# TC264MCU.net
KiCad netlist of a schematic drawn in Altium Designer
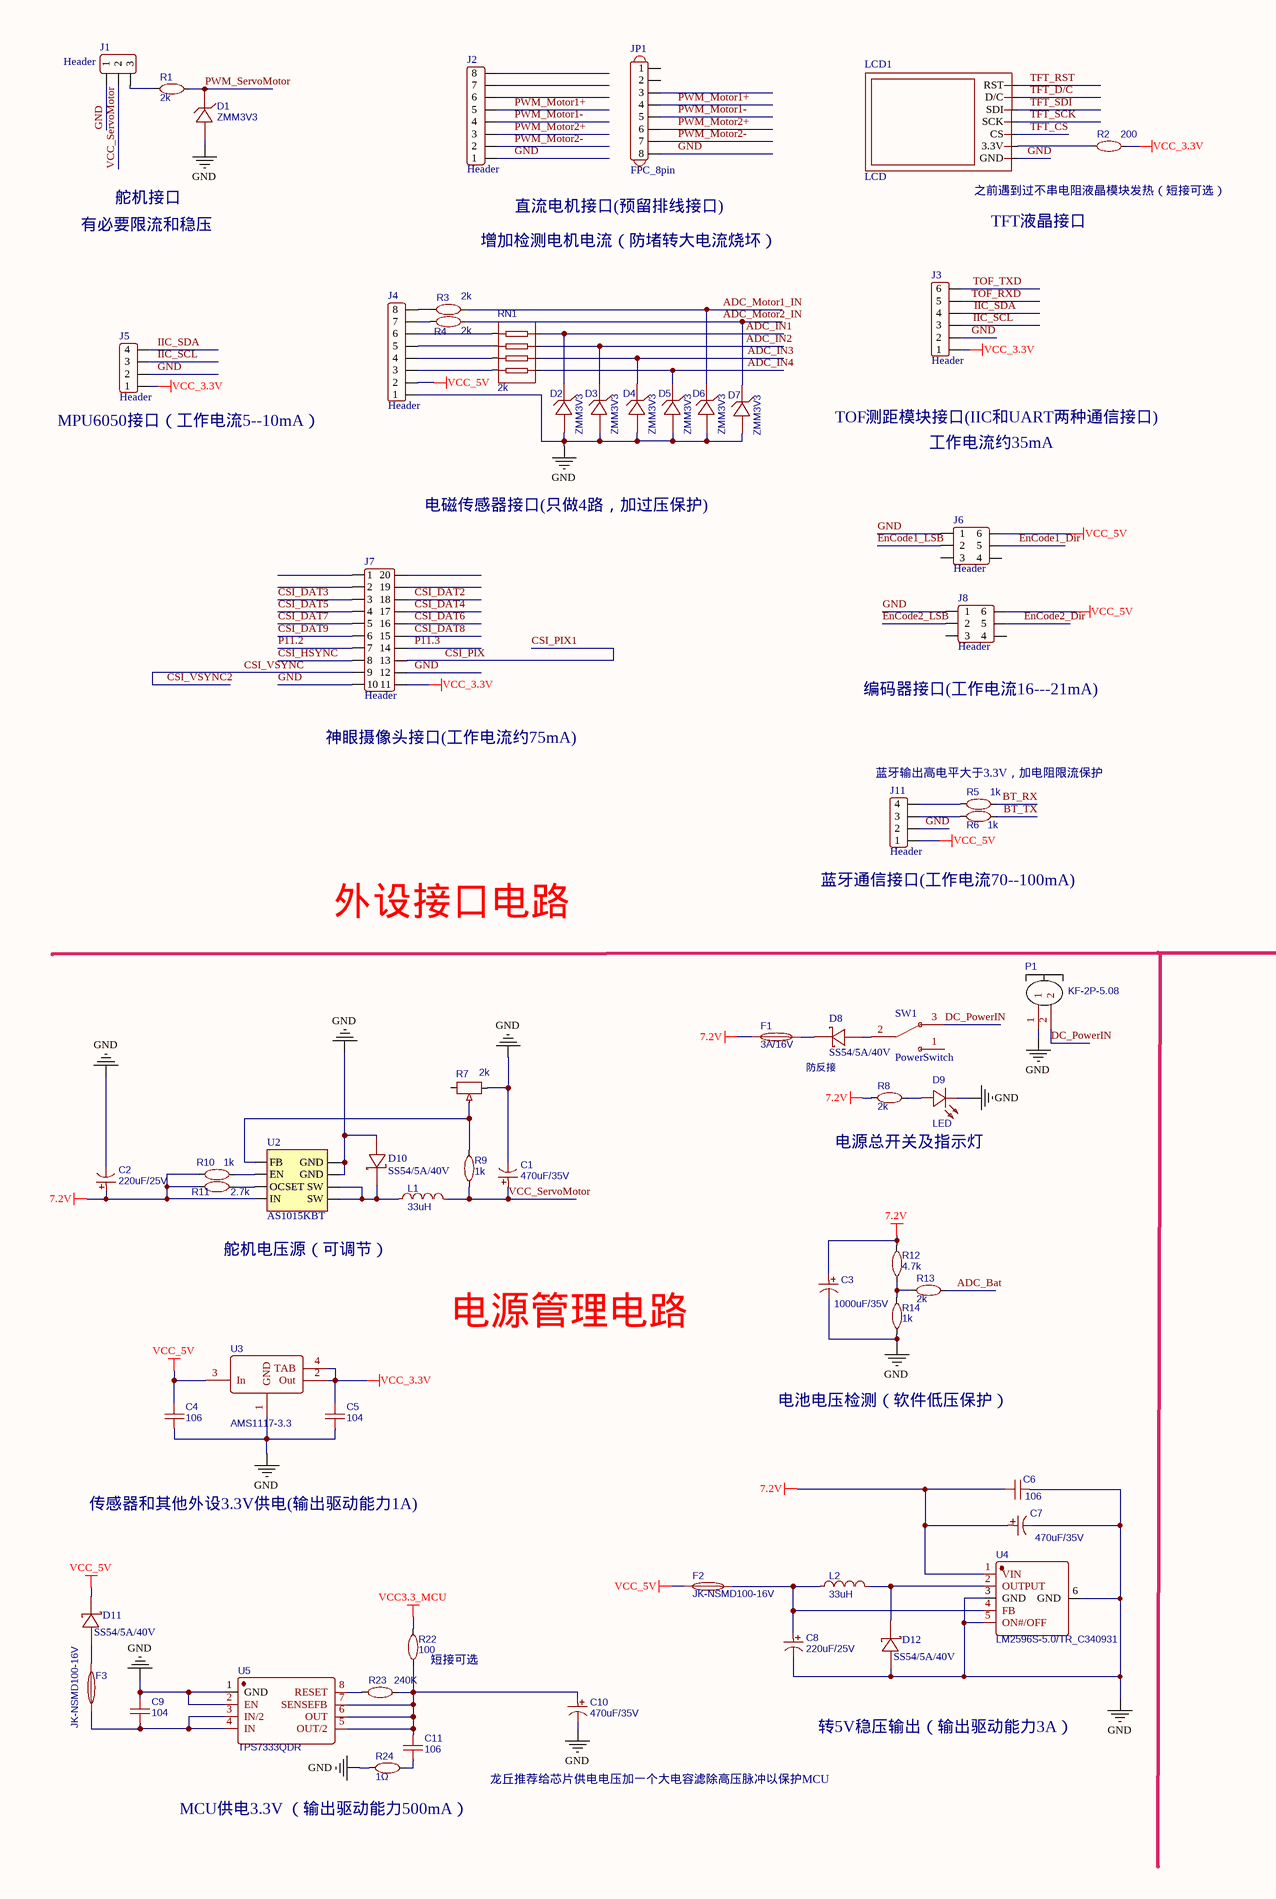
[diagram p0: TC264MCU.SchDoc, left]
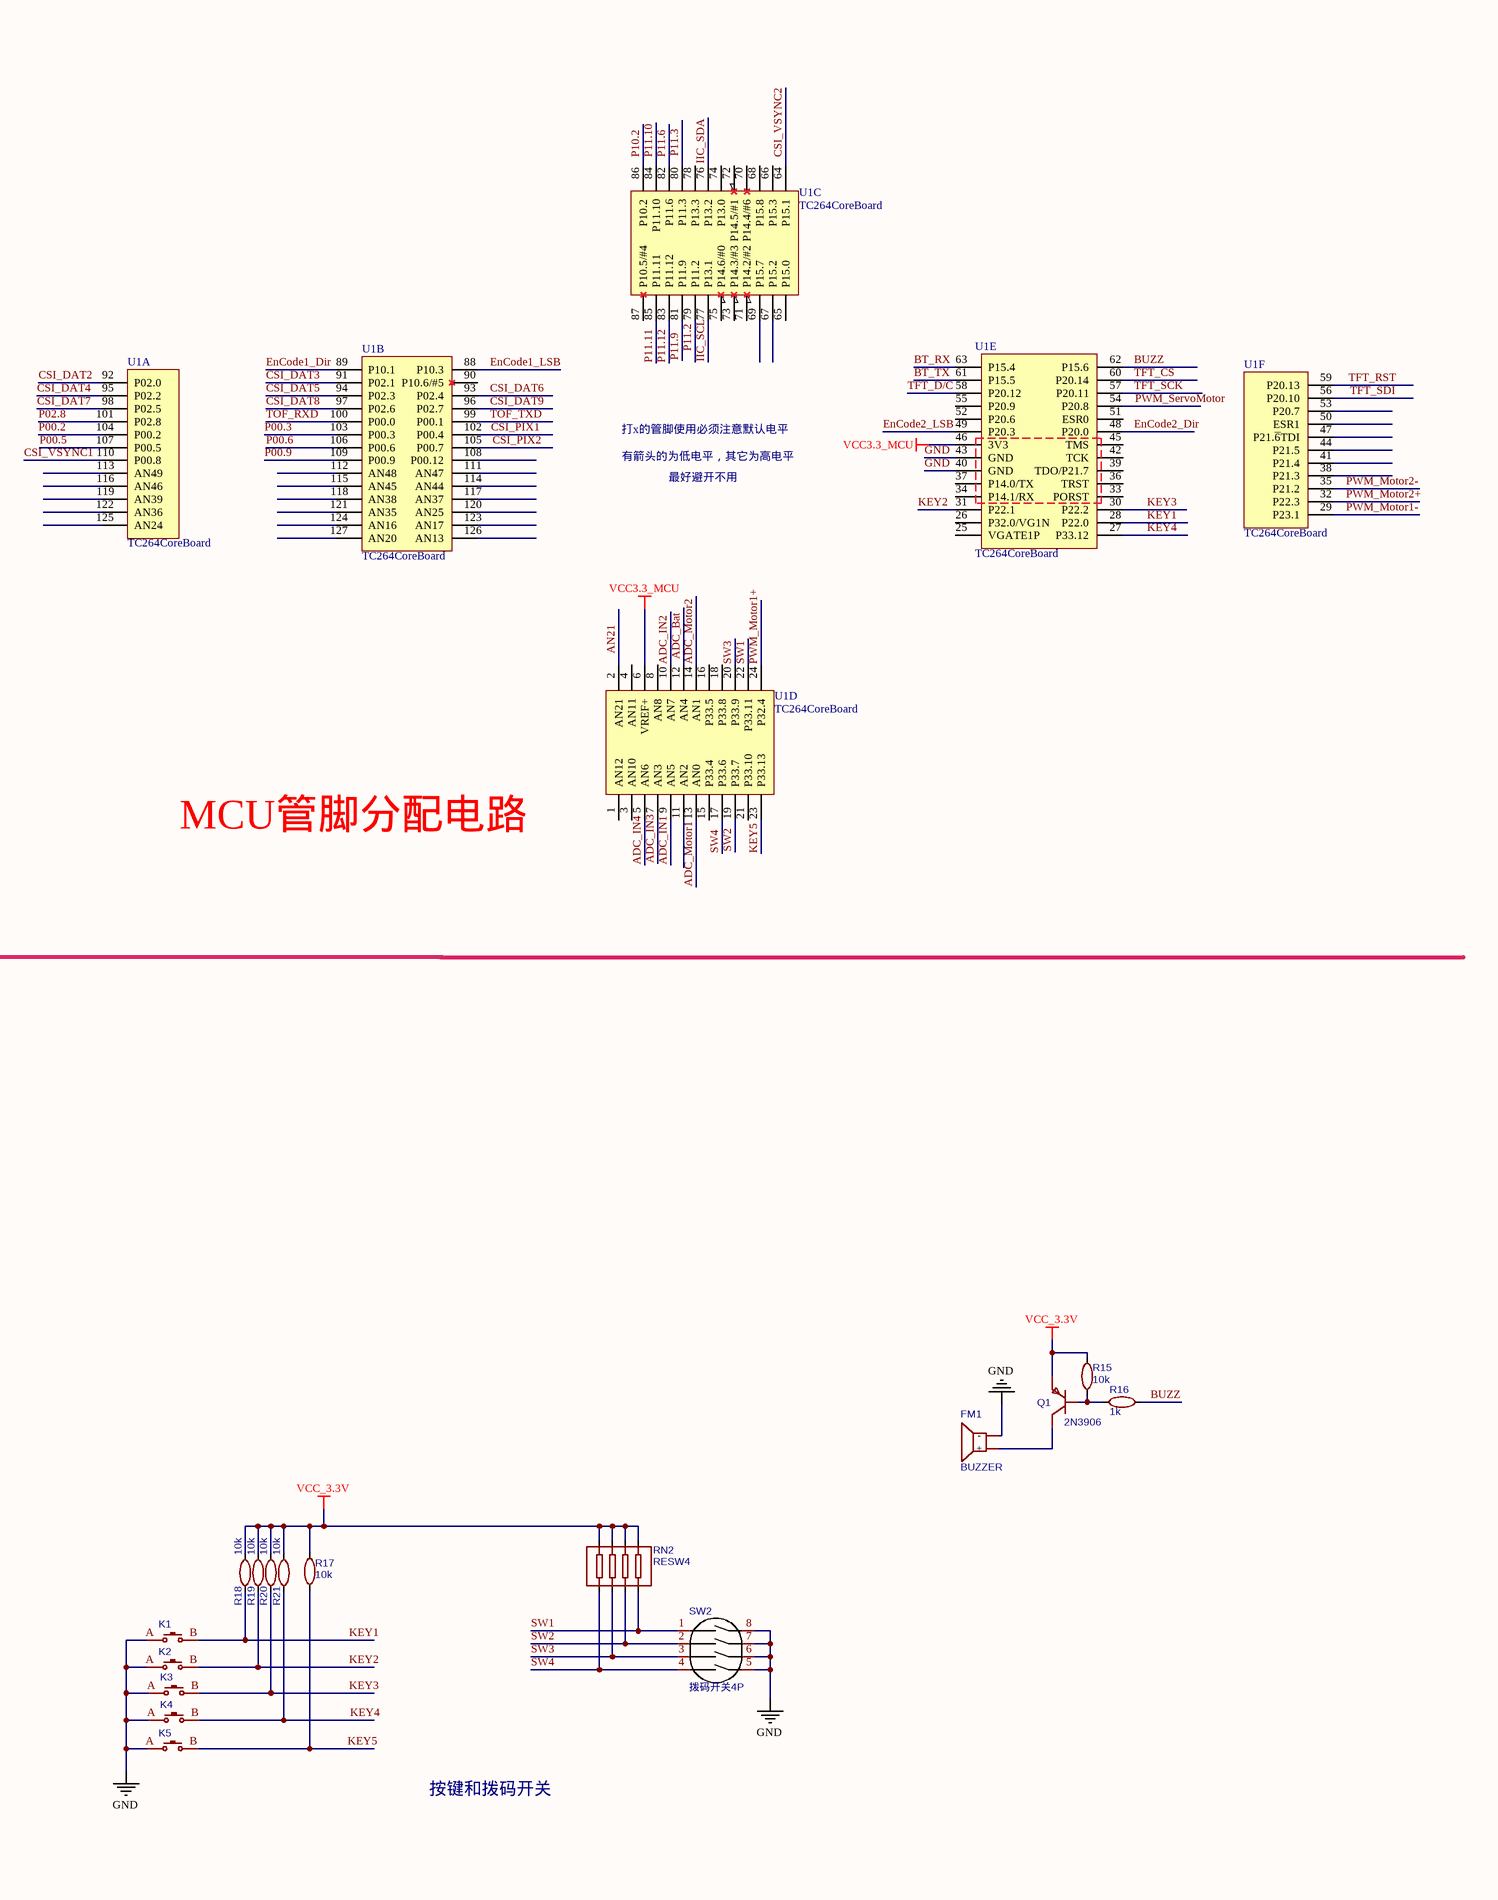
[diagram p1: TC264MCU.SchDoc, right]

(export (version "E")
  (design (tool "Eeschema 10.0.6"))
  (components
    (comp (ref "C1")
      (value "470uF/35V")
      (footprint "CAPE_SMD_G_10.6")
      (description "贴片电解电容")
      (fields
        (field (name "BOM_MANUFACTURER PART") "RVT1C221M0607")
        (field (name "BOM_SUPPLIER PART") "C72496")
      )
      (libsource (lib "") (part "CAP_E_SMD_1"))
    )
    (comp (ref "C2")
      (value "220uF/25V")
      (footprint "CAPE_SMD_F_8.4")
      (description "贴片电解电容")
      (fields
        (field (name "BOM_MANUFACTURER PART") "RVT1C221M0607")
        (field (name "BOM_SUPPLIER PART") "C72496")
      )
      (libsource (lib "") (part "CAP_E_SMD_1"))
    )
    (comp (ref "C3")
      (value "1000uF/35V")
      (footprint "CAPE_SMD_G_10.6")
      (description "贴片电解电容")
      (fields
        (field (name "BOM_MANUFACTURER PART") "RVT1C221M0607")
        (field (name "BOM_SUPPLIER PART") "C72496")
      )
      (libsource (lib "") (part "CAP_E_SMD_1"))
    )
    (comp (ref "C4")
      (value "106")
      (footprint "CAP_0603")
      (fields
        (field (name "BOM_SUPPLIER PART") "C307348")
        (field (name "BOM_MANUFACTURER PART") "CL10B104KB8WPNC")
        (field (name "CONTRIBUTOR") "LCSC")
      )
      (libsource (lib "LTC_Library1") (part "CAP_0603"))
    )
    (comp (ref "C5")
      (value "104")
      (footprint "CAP_0603")
      (fields
        (field (name "BOM_SUPPLIER PART") "C307348")
        (field (name "BOM_MANUFACTURER PART") "CL10B104KB8WPNC")
        (field (name "CONTRIBUTOR") "LCSC")
      )
      (libsource (lib "LTC_Library1") (part "CAP_0603"))
    )
    (comp (ref "C6")
      (value "106")
      (footprint "CAP_0603")
      (fields
        (field (name "BOM_SUPPLIER PART") "C307348")
        (field (name "BOM_MANUFACTURER PART") "CL10B104KB8WPNC")
        (field (name "CONTRIBUTOR") "LCSC")
      )
      (libsource (lib "LTC_Library1") (part "CAP_0603"))
    )
    (comp (ref "C7")
      (value "470uF/35V")
      (footprint "CAPE_SMD_G_10.6")
      (description "贴片电解电容")
      (fields
        (field (name "BOM_MANUFACTURER PART") "RVT1C221M0607")
        (field (name "BOM_SUPPLIER PART") "C72496")
      )
      (libsource (lib "LTC_Library1") (part "CAP_E_SMD"))
    )
    (comp (ref "C8")
      (value "220uF/25V")
      (footprint "CAPE_SMD_F_8.4")
      (description "贴片电解电容")
      (fields
        (field (name "BOM_MANUFACTURER PART") "RVT1C221M0607")
        (field (name "BOM_SUPPLIER PART") "C72496")
      )
      (libsource (lib "") (part "CAP_E_SMD_1"))
    )
    (comp (ref "C9")
      (value "104")
      (footprint "CAP_0603")
      (fields
        (field (name "BOM_SUPPLIER PART") "C307348")
        (field (name "BOM_MANUFACTURER PART") "CL10B104KB8WPNC")
        (field (name "CONTRIBUTOR") "LCSC")
      )
      (libsource (lib "LTC_Library1") (part "CAP_0603"))
    )
    (comp (ref "C10")
      (value "470uF/35V")
      (footprint "CAPE_SMD_G_10.6")
      (description "贴片电解电容")
      (fields
        (field (name "BOM_MANUFACTURER PART") "RVT1C221M0607")
        (field (name "BOM_SUPPLIER PART") "C72496")
      )
      (libsource (lib "") (part "CAP_E_SMD_1"))
    )
    (comp (ref "C11")
      (value "106")
      (footprint "CAP_0603")
      (fields
        (field (name "BOM_SUPPLIER PART") "C307348")
        (field (name "BOM_MANUFACTURER PART") "CL10B104KB8WPNC")
        (field (name "CONTRIBUTOR") "LCSC")
      )
      (libsource (lib "LTC_Library1") (part "CAP_0603"))
    )
    (comp (ref "D1")
      (value "ZMM3V3")
      (footprint "LL-34_L3.5-W1.5-RD")
      (fields (field (name "BOM_SUPPLIER PART") "C8056"))
      (libsource (lib "SmartCar_Library") (part "ZMM3V3"))
    )
    (comp (ref "D2")
      (value "ZMM3V3")
      (footprint "LL-34_L3.5-W1.5-RD")
      (fields (field (name "BOM_SUPPLIER PART") "C8056"))
      (libsource (lib "SmartCar_Library") (part "ZMM3V3"))
    )
    (comp (ref "D3")
      (value "ZMM3V3")
      (footprint "LL-34_L3.5-W1.5-RD")
      (fields (field (name "BOM_SUPPLIER PART") "C8056"))
      (libsource (lib "SmartCar_Library") (part "ZMM3V3"))
    )
    (comp (ref "D4")
      (value "ZMM3V3")
      (footprint "LL-34_L3.5-W1.5-RD")
      (fields (field (name "BOM_SUPPLIER PART") "C8056"))
      (libsource (lib "SmartCar_Library") (part "ZMM3V3"))
    )
    (comp (ref "D5")
      (value "ZMM3V3")
      (footprint "LL-34_L3.5-W1.5-RD")
      (fields (field (name "BOM_SUPPLIER PART") "C8056"))
      (libsource (lib "SmartCar_Library") (part "ZMM3V3"))
    )
    (comp (ref "D6")
      (value "ZMM3V3")
      (footprint "LL-34_L3.5-W1.5-RD")
      (fields (field (name "BOM_SUPPLIER PART") "C8056"))
      (libsource (lib "SmartCar_Library") (part "ZMM3V3"))
    )
    (comp (ref "D7")
      (value "ZMM3V3")
      (footprint "LL-34_L3.5-W1.5-RD")
      (fields (field (name "BOM_SUPPLIER PART") "C8056"))
      (libsource (lib "SmartCar_Library") (part "ZMM3V3"))
    )
    (comp (ref "D8")
      (value "SS54/5A/40V")
      (footprint "DO214_SMA")
      (libsource (lib "LTC_Library1") (part "SS54"))
    )
    (comp (ref "D9")
      (value "LED")
      (footprint "LED_0603_B")
      (description "发光LED")
      (fields
        (field (name "BOM_MANUFACTURER PART") "D-G080508G1")
        (field (name "BOM_SUPPLIER PART") "C107402")
        (field (name "CONTRIBUTOR") "LCSC")
      )
      (libsource (lib "LTC_Library1") (part "LED_0603"))
    )
    (comp (ref "D10")
      (value "SS54/5A/40V")
      (footprint "DO214_SMA")
      (libsource (lib "LTC_Library1") (part "SS54"))
    )
    (comp (ref "D11")
      (value "SS54/5A/40V")
      (footprint "DO214_SMA")
      (libsource (lib "LTC_Library1") (part "SS54"))
    )
    (comp (ref "D12")
      (value "SS54/5A/40V")
      (footprint "DO214_SMA")
      (libsource (lib "LTC_Library1") (part "SS54"))
    )
    (comp (ref "F1")
      (value "3A/16V")
      (footprint "F1206")
      (fields
        (field (name "BOM_SUPPLIER PART") "C369161")
        (field (name "BOM_MANUFACTURER PART") "JK-NSMD100-16V")
        (field (name "CONTRIBUTOR") "LCSC")
      )
      (libsource (lib "SmartCar_Library") (part "JK-NSMD100-16V"))
    )
    (comp (ref "F2")
      (value "JK-NSMD100-16V")
      (footprint "F1206")
      (fields (field (name "BOM_SUPPLIER PART") "C369161") (field (name "CONTRIBUTOR") "LCSC"))
      (libsource (lib "SmartCar_Library") (part "JK-NSMD100-16V"))
    )
    (comp (ref "F3")
      (value "JK-NSMD100-16V")
      (footprint "F1206")
      (fields (field (name "BOM_SUPPLIER PART") "C369161") (field (name "CONTRIBUTOR") "LCSC"))
      (libsource (lib "SmartCar_Library") (part "JK-NSMD100-16V"))
    )
    (comp (ref "FM1")
      (value "BUZZER")
      (footprint "BUZZ-12*7.5")
      (description "蜂鸣器")
      (fields (field (name "BOM_MANUFACTURER PART") "TMB12A12") (field (name "BOM_SUPPLIER PART") "C96079"))
      (libsource (lib "LTC_Library1") (part "BUZZER"))
    )
    (comp (ref "J1")
      (value "Header")
      (footprint "Header 2.54X3")
      (libsource (lib "LTC_Library1") (part "Header 2.54_3"))
    )
    (comp (ref "J2")
      (value "Header")
      (footprint "Header 2.54X8")
      (libsource (lib "LTC_Library1") (part "Header 2.54_8"))
    )
    (comp (ref "J3")
      (value "Header")
      (footprint "Header 2.54X6")
      (libsource (lib "LTC_Library1") (part "Header 2.54_6"))
    )
    (comp (ref "J4")
      (value "Header")
      (footprint "Header 2.54X8")
      (libsource (lib "LTC_Library1") (part "Header 2.54_8"))
    )
    (comp (ref "J5")
      (value "Header")
      (footprint "Header 2.54X4")
      (libsource (lib "LTC_Library1") (part "Header 2.54_4"))
    )
    (comp (ref "J6")
      (value "Header")
      (footprint "Header 2.54_2X3")
      (libsource (lib "LTC_Library1") (part "Header 2.54_2X3"))
    )
    (comp (ref "J7")
      (value "Header")
      (footprint "Header F 2.54_2x10")
      (libsource (lib "LTC_Library1") (part "Header 2.54_2X10"))
    )
    (comp (ref "J8")
      (value "Header")
      (footprint "Header 2.54_2X3")
      (libsource (lib "LTC_Library1") (part "Header 2.54_2X3"))
    )
    (comp (ref "J11")
      (value "Header")
      (footprint "Header F 2.54X4")
      (libsource (lib "LTC_Library1") (part "Header 2.54_4"))
    )
    (comp (ref "JP1")
      (value "FPC_8pin")
      (footprint "FPC_1.0_8P")
      (libsource (lib "LTC_Library1") (part "FPC_8pin"))
    )
    (comp (ref "K1")
      (value "TS-Button_2P")
      (footprint "SW_SMD_6.1*3.7")
      (description "贴片按键 3*6*2.5")
      (fields
        (field (name "BOM_SUPPLIER PART") "C455236")
        (field (name "BOM_MANUFACTURER PART") "TS-1007S-26")
        (field (name "CONTRIBUTOR") "LCSC")
      )
      (libsource (lib "LTC_Library1") (part "TS-Button_2P"))
    )
    (comp (ref "K2")
      (value "TS-Button_2P")
      (footprint "SW_SMD_6.1*3.7")
      (description "贴片按键 3*6*2.5")
      (fields
        (field (name "BOM_SUPPLIER PART") "C455236")
        (field (name "BOM_MANUFACTURER PART") "TS-1007S-26")
        (field (name "CONTRIBUTOR") "LCSC")
      )
      (libsource (lib "LTC_Library1") (part "TS-Button_2P"))
    )
    (comp (ref "K3")
      (value "TS-Button_2P")
      (footprint "SW_SMD_6.1*3.7")
      (description "贴片按键 3*6*2.5")
      (fields
        (field (name "BOM_SUPPLIER PART") "C455236")
        (field (name "BOM_MANUFACTURER PART") "TS-1007S-26")
        (field (name "CONTRIBUTOR") "LCSC")
      )
      (libsource (lib "LTC_Library1") (part "TS-Button_2P"))
    )
    (comp (ref "K4")
      (value "TS-Button_2P")
      (footprint "SW_SMD_6.1*3.7")
      (description "贴片按键 3*6*2.5")
      (fields
        (field (name "BOM_SUPPLIER PART") "C455236")
        (field (name "BOM_MANUFACTURER PART") "TS-1007S-26")
        (field (name "CONTRIBUTOR") "LCSC")
      )
      (libsource (lib "LTC_Library1") (part "TS-Button_2P"))
    )
    (comp (ref "K5")
      (value "TS-Button_2P")
      (footprint "SW_SMD_6.1*3.7")
      (description "贴片按键 3*6*2.5")
      (fields
        (field (name "BOM_SUPPLIER PART") "C455236")
        (field (name "BOM_MANUFACTURER PART") "TS-1007S-26")
        (field (name "CONTRIBUTOR") "LCSC")
      )
      (libsource (lib "LTC_Library1") (part "TS-Button_2P"))
    )
    (comp (ref "L1")
      (value "33uH")
      (footprint "IND-SMD_L8.0-W8.0")
      (fields
        (field (name "BOM_SUPPLIER PART") "C295130")
        (field (name "BOM_MANUFACTURER PART") "NLV25T-330J-EF")
        (field (name "CONTRIBUTOR") "LCSC")
      )
      (libsource (lib "SmartCar_Library") (part "Inductor"))
    )
    (comp (ref "L2")
      (value "33uH")
      (footprint "IND-SMD_L8.0-W8.0")
      (fields
        (field (name "BOM_SUPPLIER PART") "C295130")
        (field (name "BOM_MANUFACTURER PART") "NLV25T-330J-EF")
        (field (name "CONTRIBUTOR") "LCSC")
      )
      (libsource (lib "SmartCar_Library") (part "Inductor"))
    )
    (comp (ref "LCD1")
      (value "LCD")
      (footprint "TFT_LCD")
      (libsource (lib "SmartCar_Library") (part "TFT-LCD"))
    )
    (comp (ref "P1")
      (value "KF-2P-5.08")
      (footprint "KF_2P-5.08")
      (description "端子2P")
      (fields
        (field (name "BOM_MANUFACTURER PART") "WJ500H-5.08-2P")
        (field (name "BOM_SUPPLIER PART") "C8478")
      )
      (libsource (lib "LTC_Library1") (part "KF-2P-5.08"))
    )
    (comp (ref "Q1")
      (value "2N3906")
      (footprint "TO_92A")
      (description "三极管PNP")
      (fields (field (name "BOM_SUPPLIER PART") "C305396") (field (name "CONTRIBUTOR") "LCSC"))
      (libsource (lib "LTC_Library1") (part "2N3906"))
    )
    (comp (ref "R1")
      (value "2k")
      (footprint "RES_0603")
      (fields
        (field (name "BOM_MANUFACTURER PART") "RC0402JR-07100KL")
        (field (name "BOM_SUPPLIER PART") "C106234")
      )
      (libsource (lib "LTC_Library1") (part "RES_0603"))
    )
    (comp (ref "R2")
      (value "200")
      (footprint "RES_0603")
      (fields
        (field (name "BOM_MANUFACTURER PART") "RC0402JR-07100KL")
        (field (name "BOM_SUPPLIER PART") "C106234")
      )
      (libsource (lib "LTC_Library1") (part "RES_0603"))
    )
    (comp (ref "R3")
      (value "2k")
      (footprint "RES_0603")
      (fields
        (field (name "BOM_MANUFACTURER PART") "RC0402JR-07100KL")
        (field (name "BOM_SUPPLIER PART") "C106234")
      )
      (libsource (lib "LTC_Library1") (part "RES_0603"))
    )
    (comp (ref "R4")
      (value "2k")
      (footprint "RES_0603")
      (fields
        (field (name "BOM_MANUFACTURER PART") "RC0402JR-07100KL")
        (field (name "BOM_SUPPLIER PART") "C106234")
      )
      (libsource (lib "LTC_Library1") (part "RES_0603"))
    )
    (comp (ref "R5")
      (value "1k")
      (footprint "RES_0603")
      (fields
        (field (name "BOM_MANUFACTURER PART") "RC0402JR-07100KL")
        (field (name "BOM_SUPPLIER PART") "C106234")
      )
      (libsource (lib "LTC_Library1") (part "RES_0603"))
    )
    (comp (ref "R6")
      (value "1k")
      (footprint "RES_0603")
      (fields
        (field (name "BOM_MANUFACTURER PART") "RC0402JR-07100KL")
        (field (name "BOM_SUPPLIER PART") "C106234")
      )
      (libsource (lib "LTC_Library1") (part "RES_0603"))
    )
    (comp (ref "R7")
      (value "2k")
      (footprint "RES_POT-3296W")
      (description "可调电阻3296W")
      (fields
        (field (name "BOM_SUPPLIER PART") "C118963")
        (field (name "BOM_MANUFACTURER PART") "3296W-1-104")
        (field (name "CONTRIBUTOR") "LCSC")
      )
      (libsource (lib "LTC_Library1") (part "RES_POT-3296W"))
    )
    (comp (ref "R8")
      (value "2k")
      (footprint "RES_0603")
      (fields
        (field (name "BOM_MANUFACTURER PART") "RC0402JR-07100KL")
        (field (name "BOM_SUPPLIER PART") "C106234")
      )
      (libsource (lib "LTC_Library1") (part "RES_0603"))
    )
    (comp (ref "R9")
      (value "1k")
      (footprint "RES_0603")
      (fields
        (field (name "BOM_MANUFACTURER PART") "RC0402JR-07100KL")
        (field (name "BOM_SUPPLIER PART") "C106234")
      )
      (libsource (lib "LTC_Library1") (part "RES_0603"))
    )
    (comp (ref "R10")
      (value "1k")
      (footprint "RES_0603")
      (fields
        (field (name "BOM_MANUFACTURER PART") "RC0402JR-07100KL")
        (field (name "BOM_SUPPLIER PART") "C106234")
      )
      (libsource (lib "LTC_Library1") (part "RES_0603"))
    )
    (comp (ref "R11")
      (value "2.7k")
      (footprint "RES_0603")
      (fields
        (field (name "BOM_MANUFACTURER PART") "RC0402JR-07100KL")
        (field (name "BOM_SUPPLIER PART") "C106234")
      )
      (libsource (lib "LTC_Library1") (part "RES_0603"))
    )
    (comp (ref "R12")
      (value "4.7k")
      (footprint "RES_0603")
      (fields
        (field (name "BOM_MANUFACTURER PART") "RC0402JR-07100KL")
        (field (name "BOM_SUPPLIER PART") "C106234")
      )
      (libsource (lib "LTC_Library1") (part "RES_0603"))
    )
    (comp (ref "R13")
      (value "2k")
      (footprint "RES_0603")
      (fields
        (field (name "BOM_MANUFACTURER PART") "RC0402JR-07100KL")
        (field (name "BOM_SUPPLIER PART") "C106234")
      )
      (libsource (lib "LTC_Library1") (part "RES_0603"))
    )
    (comp (ref "R14")
      (value "1k")
      (footprint "RES_0603")
      (fields
        (field (name "BOM_MANUFACTURER PART") "RC0402JR-07100KL")
        (field (name "BOM_SUPPLIER PART") "C106234")
      )
      (libsource (lib "LTC_Library1") (part "RES_0603"))
    )
    (comp (ref "R15")
      (value "10k")
      (footprint "RES_0603")
      (fields
        (field (name "BOM_MANUFACTURER PART") "RC0402JR-07100KL")
        (field (name "BOM_SUPPLIER PART") "C106234")
      )
      (libsource (lib "LTC_Library1") (part "RES_0603"))
    )
    (comp (ref "R16")
      (value "1k")
      (footprint "RES_0603")
      (fields
        (field (name "BOM_MANUFACTURER PART") "RC0402JR-07100KL")
        (field (name "BOM_SUPPLIER PART") "C106234")
      )
      (libsource (lib "LTC_Library1") (part "RES_0603"))
    )
    (comp (ref "R17")
      (value "10k")
      (footprint "RES_0603")
      (fields
        (field (name "BOM_MANUFACTURER PART") "RC0402JR-07100KL")
        (field (name "BOM_SUPPLIER PART") "C106234")
      )
      (libsource (lib "LTC_Library1") (part "RES_0603"))
    )
    (comp (ref "R18")
      (value "10k")
      (footprint "RES_0603")
      (fields
        (field (name "BOM_MANUFACTURER PART") "RC0402JR-07100KL")
        (field (name "BOM_SUPPLIER PART") "C106234")
      )
      (libsource (lib "LTC_Library1") (part "RES_0603"))
    )
    (comp (ref "R19")
      (value "10k")
      (footprint "RES_0603")
      (fields
        (field (name "BOM_MANUFACTURER PART") "RC0402JR-07100KL")
        (field (name "BOM_SUPPLIER PART") "C106234")
      )
      (libsource (lib "LTC_Library1") (part "RES_0603"))
    )
    (comp (ref "R20")
      (value "10k")
      (footprint "RES_0603")
      (fields
        (field (name "BOM_MANUFACTURER PART") "RC0402JR-07100KL")
        (field (name "BOM_SUPPLIER PART") "C106234")
      )
      (libsource (lib "LTC_Library1") (part "RES_0603"))
    )
    (comp (ref "R21")
      (value "10k")
      (footprint "RES_0603")
      (fields
        (field (name "BOM_MANUFACTURER PART") "RC0402JR-07100KL")
        (field (name "BOM_SUPPLIER PART") "C106234")
      )
      (libsource (lib "LTC_Library1") (part "RES_0603"))
    )
    (comp (ref "R22")
      (value "100")
      (footprint "RES_0603")
      (fields
        (field (name "BOM_MANUFACTURER PART") "RC0402JR-07100KL")
        (field (name "BOM_SUPPLIER PART") "C106234")
      )
      (libsource (lib "LTC_Library1") (part "RES_0603"))
    )
    (comp (ref "R23")
      (value "240K")
      (footprint "RES_0603")
      (fields
        (field (name "BOM_MANUFACTURER PART") "RC0402JR-07100KL")
        (field (name "BOM_SUPPLIER PART") "C106234")
      )
      (libsource (lib "LTC_Library1") (part "RES_0603"))
    )
    (comp (ref "R24")
      (value "1Ω")
      (footprint "RES_0603")
      (fields
        (field (name "BOM_MANUFACTURER PART") "RC0402JR-07100KL")
        (field (name "BOM_SUPPLIER PART") "C106234")
      )
      (libsource (lib "LTC_Library1") (part "RES_0603"))
    )
    (comp (ref "RN1")
      (value "2k")
      (footprint "RES-ARRAY-SMD_0603-8P-L3.2-W1.6-BL")
      (fields
        (field (name "BOM_MANUFACTURER PART") "YC164-JR-0710KL")
        (field (name "BOM_SUPPLIER PART") "C107374")
      )
      (libsource (lib "SmartCar_Library") (part "RESW4"))
    )
    (comp (ref "RN2")
      (value "RESW4")
      (footprint "RES-ARRAY-SMD_0603-8P-L3.2-W1.6-BL")
      (fields
        (field (name "BOM_MANUFACTURER PART") "YC164-JR-0710KL")
        (field (name "BOM_SUPPLIER PART") "C107374")
      )
      (libsource (lib "SmartCar_Library") (part "RESW4"))
    )
    (comp (ref "SW1")
      (value "PowerSwitch")
      (footprint "SW-TH_K3-1260D-K1")
      (libsource (lib "SmartCar_Library") (part "PowerSwitch"))
    )
    (comp (ref "SW2")
      (value "拨码开关4P")
      (footprint "MCEMR-04-T")
      (description "DIP_4PX2*2.54")
      (fields
        (field (name "BOM_MANUFACTURER PART") "VDG/S-04HG-R")
        (field (name "BOM_SUPPLIER PART") "C15781")
      )
      (libsource (lib "LTC_Library1") (part "拨码开关4P"))
    )
    (comp (ref "U1")
      (value "TC264CoreBoard")
      (footprint "LQ-TC264-SYSVC-S")
      (libsource (lib "SmartCar_Library") (part "TC264CoreBoard"))
    )
    (comp (ref "U2")
      (value "AS1015KBT")
      (footprint "SOIC-8_150MIL")
      (libsource (lib "SmartCar_Library") (part "AS1015KBT"))
    )
    (comp (ref "U3")
      (value "AMS1117-3.3")
      (footprint "SOT-223_3")
      (fields (field (name "BOM_SUPPLIER PART") "C165482") (field (name "CONTRIBUTOR") "LCSC"))
      (libsource (lib "LTC_Library1") (part "AMS1117-3.3"))
    )
    (comp (ref "U4")
      (value "LM2596S-5.0/TR_C340931")
      (footprint "TO-263_5")
      (fields
        (field (name "BOM_SUPPLIER PART") "C340931")
        (field (name "BOM_MANUFACTURER PART") "LM2596S-5.0/TR")
        (field (name "CONTRIBUTOR") "LCSC")
      )
      (libsource (lib "LTC_Library1") (part "LM2596S-5.0/TR_C340931"))
    )
    (comp (ref "U5")
      (value "TPS7333QDR")
      (footprint "SOIC-8_150MIL")
      (fields (field (name "BOM_SUPPLIER PART") "C23791"))
      (libsource (lib "LTC_Library1") (part "TPS7333QDR"))
    )
  )
  (nets
    (net (code "1") (name "/ADC_Bat") (class "Default")
      (node (ref "R13") (pin "2") (pinfunction "2_2") (pintype "passive"))
      (node (ref "U1") (pin "12") (pinfunction "AN4_12") (pintype "passive"))
    )
    (net (code "2") (name "/ADC_IN1") (class "Default")
      (node (ref "D2") (pin "1") (pinfunction "C_1") (pintype "passive"))
      (node (ref "RN1") (pin "8") (pinfunction "8_8") (pintype "passive"))
      (node (ref "U1") (pin "9") (pinfunction "AN5_9") (pintype "passive"))
    )
    (net (code "3") (name "/ADC_IN2") (class "Default")
      (node (ref "D3") (pin "1") (pinfunction "C_1") (pintype "passive"))
      (node (ref "RN1") (pin "7") (pinfunction "7_7") (pintype "passive"))
      (node (ref "U1") (pin "10") (pinfunction "AN7_10") (pintype "passive"))
    )
    (net (code "4") (name "/ADC_IN3") (class "Default")
      (node (ref "D4") (pin "1") (pinfunction "C_1") (pintype "passive"))
      (node (ref "RN1") (pin "6") (pinfunction "6_6") (pintype "passive"))
      (node (ref "U1") (pin "7") (pinfunction "AN3_7") (pintype "passive"))
    )
    (net (code "5") (name "/ADC_IN4") (class "Default")
      (node (ref "D5") (pin "1") (pinfunction "C_1") (pintype "passive"))
      (node (ref "RN1") (pin "5") (pinfunction "5_5") (pintype "passive"))
      (node (ref "U1") (pin "5") (pinfunction "AN6_5") (pintype "passive"))
    )
    (net (code "6") (name "/ADC_Motor1") (class "Default")
      (node (ref "U1") (pin "13") (pinfunction "AN0_13") (pintype "passive"))
    )
    (net (code "7") (name "/ADC_Motor1_IN") (class "Default")
      (node (ref "D6") (pin "1") (pinfunction "C_1") (pintype "passive"))
      (node (ref "R3") (pin "1") (pinfunction "1_1") (pintype "passive"))
    )
    (net (code "8") (name "/ADC_Motor2") (class "Default")
      (node (ref "U1") (pin "14") (pinfunction "AN1_14") (pintype "passive"))
    )
    (net (code "9") (name "/ADC_Motor2_IN") (class "Default")
      (node (ref "D7") (pin "1") (pinfunction "C_1") (pintype "passive"))
      (node (ref "R4") (pin "1") (pinfunction "1_1") (pintype "passive"))
    )
    (net (code "10") (name "/AN21") (class "Default")
      (node (ref "U1") (pin "2") (pinfunction "AN21_2") (pintype "passive"))
    )
    (net (code "11") (name "/BT_RX") (class "Default")
      (node (ref "R5") (pin "1") (pinfunction "1_1") (pintype "passive"))
      (node (ref "U1") (pin "63") (pinfunction "P15.4_63") (pintype "passive"))
    )
    (net (code "12") (name "/BT_TX") (class "Default")
      (node (ref "R6") (pin "1") (pinfunction "1_1") (pintype "passive"))
      (node (ref "U1") (pin "61") (pinfunction "P15.5_61") (pintype "passive"))
    )
    (net (code "13") (name "/BUZZ") (class "Default")
      (node (ref "R16") (pin "1") (pinfunction "1_1") (pintype "passive"))
      (node (ref "U1") (pin "62") (pinfunction "P15.6_62") (pintype "passive"))
    )
    (net (code "14") (name "/CSI_DAT2") (class "Default")
      (node (ref "J7") (pin "18") (pinfunction "18_18") (pintype "passive"))
      (node (ref "U1") (pin "92") (pinfunction "P02.0_92") (pintype "passive"))
    )
    (net (code "15") (name "/CSI_DAT3") (class "Default")
      (node (ref "J7") (pin "3") (pinfunction "3_3") (pintype "passive"))
      (node (ref "U1") (pin "91") (pinfunction "P02.1_91") (pintype "passive"))
    )
    (net (code "16") (name "/CSI_DAT4") (class "Default")
      (node (ref "J7") (pin "17") (pinfunction "17_17") (pintype "passive"))
      (node (ref "U1") (pin "95") (pinfunction "P02.2_95") (pintype "passive"))
    )
    (net (code "17") (name "/CSI_DAT5") (class "Default")
      (node (ref "J7") (pin "4") (pinfunction "4_4") (pintype "passive"))
      (node (ref "U1") (pin "94") (pinfunction "P02.3_94") (pintype "passive"))
    )
    (net (code "18") (name "/CSI_DAT6") (class "Default")
      (node (ref "J7") (pin "16") (pinfunction "16_16") (pintype "passive"))
      (node (ref "U1") (pin "93") (pinfunction "P02.4_93") (pintype "passive"))
    )
    (net (code "19") (name "/CSI_DAT7") (class "Default")
      (node (ref "J7") (pin "5") (pinfunction "5_5") (pintype "passive"))
      (node (ref "U1") (pin "98") (pinfunction "P02.5_98") (pintype "passive"))
    )
    (net (code "20") (name "/CSI_DAT8") (class "Default")
      (node (ref "J7") (pin "15") (pinfunction "15_15") (pintype "passive"))
      (node (ref "U1") (pin "97") (pinfunction "P02.6_97") (pintype "passive"))
    )
    (net (code "21") (name "/CSI_DAT9") (class "Default")
      (node (ref "J7") (pin "6") (pinfunction "6_6") (pintype "passive"))
      (node (ref "U1") (pin "96") (pinfunction "P02.7_96") (pintype "passive"))
    )
    (net (code "22") (name "/CSI_HSYNC") (class "Default")
      (node (ref "J7") (pin "8") (pinfunction "8_8") (pintype "passive"))
    )
    (net (code "23") (name "/CSI_PIX") (class "Default")
      (node (ref "J7") (pin "13") (pinfunction "13_13") (pintype "passive"))
      (node (ref "U1") (pin "102") (pinfunction "P00.4_102") (pintype "passive"))
    )
    (net (code "24") (name "/CSI_PIX2") (class "Default")
      (node (ref "U1") (pin "105") (pinfunction "P00.7_105") (pintype "passive"))
    )
    (net (code "25") (name "/CSI_VSYNC") (class "Default")
      (node (ref "J7") (pin "9") (pinfunction "9_9") (pintype "passive"))
      (node (ref "U1") (pin "64") (pinfunction "P15.1_64") (pintype "passive"))
    )
    (net (code "26") (name "/CSI_VSYNC1") (class "Default")
      (node (ref "U1") (pin "110") (pinfunction "P00.8_110") (pintype "passive"))
    )
    (net (code "27") (name "/DC_PowerIN") (class "Default")
      (node (ref "P1") (pin "2") (pinfunction "2_2") (pintype "passive"))
      (node (ref "SW1") (pin "3") (pinfunction "NC_3") (pintype "passive"))
    )
    (net (code "28") (name "/EnCode1_Dir") (class "Default")
      (node (ref "J6") (pin "5") (pinfunction "5_5") (pintype "passive"))
      (node (ref "U1") (pin "89") (pinfunction "P10.1_89") (pintype "passive"))
    )
    (net (code "29") (name "/EnCode1_LSB") (class "Default")
      (node (ref "J6") (pin "2") (pinfunction "2_2") (pintype "passive"))
      (node (ref "U1") (pin "88") (pinfunction "P10.3_88") (pintype "passive"))
    )
    (net (code "30") (name "/EnCode2_Dir") (class "Default")
      (node (ref "J8") (pin "5") (pinfunction "5_5") (pintype "passive"))
      (node (ref "U1") (pin "48") (pinfunction "P20.0_48") (pintype "passive"))
    )
    (net (code "31") (name "/EnCode2_LSB") (class "Default")
      (node (ref "J8") (pin "2") (pinfunction "2_2") (pintype "passive"))
      (node (ref "U1") (pin "49") (pinfunction "P20.3_49") (pintype "passive"))
    )
    (net (code "32") (name "/IIC_SCL") (class "Default")
      (node (ref "J3") (pin "3") (pinfunction "3_3") (pintype "passive"))
      (node (ref "J5") (pin "3") (pinfunction "3_3") (pintype "passive"))
      (node (ref "U1") (pin "77") (pinfunction "P13.1_77") (pintype "passive"))
    )
    (net (code "33") (name "/IIC_SDA") (class "Default")
      (node (ref "J3") (pin "4") (pinfunction "4_4") (pintype "passive"))
      (node (ref "J5") (pin "4") (pinfunction "4_4") (pintype "passive"))
      (node (ref "U1") (pin "76") (pinfunction "P13.2_76") (pintype "passive"))
    )
    (net (code "34") (name "/KEY1") (class "Default")
      (node (ref "K1") (pin "B") (pinfunction "B_B") (pintype "passive"))
      (node (ref "R18") (pin "1") (pinfunction "1_1") (pintype "passive"))
      (node (ref "U1") (pin "28") (pinfunction "P22.0_28") (pintype "passive"))
    )
    (net (code "35") (name "/KEY2") (class "Default")
      (node (ref "K2") (pin "B") (pinfunction "B_B") (pintype "passive"))
      (node (ref "R19") (pin "1") (pinfunction "1_1") (pintype "passive"))
      (node (ref "U1") (pin "31") (pinfunction "P22.1_31") (pintype "passive"))
    )
    (net (code "36") (name "/KEY3") (class "Default")
      (node (ref "K3") (pin "B") (pinfunction "B_B") (pintype "passive"))
      (node (ref "R20") (pin "1") (pinfunction "1_1") (pintype "passive"))
      (node (ref "U1") (pin "30") (pinfunction "P22.2_30") (pintype "passive"))
    )
    (net (code "37") (name "/KEY4") (class "Default")
      (node (ref "K4") (pin "B") (pinfunction "B_B") (pintype "passive"))
      (node (ref "R21") (pin "1") (pinfunction "1_1") (pintype "passive"))
      (node (ref "U1") (pin "27") (pinfunction "P33.12_27") (pintype "passive"))
    )
    (net (code "38") (name "/KEY5") (class "Default")
      (node (ref "K5") (pin "B") (pinfunction "B_B") (pintype "passive"))
      (node (ref "R17") (pin "1") (pinfunction "1_1") (pintype "passive"))
      (node (ref "U1") (pin "23") (pinfunction "P33.13_23") (pintype "passive"))
    )
    (net (code "39") (name "/P00.2") (class "Default")
      (node (ref "U1") (pin "104") (pinfunction "P00.2_104") (pintype "passive"))
    )
    (net (code "40") (name "/P00.3") (class "Default")
      (node (ref "U1") (pin "103") (pinfunction "P00.3_103") (pintype "passive"))
    )
    (net (code "41") (name "/P00.5") (class "Default")
      (node (ref "U1") (pin "107") (pinfunction "P00.5_107") (pintype "passive"))
    )
    (net (code "42") (name "/P00.6") (class "Default")
      (node (ref "U1") (pin "106") (pinfunction "P00.6_106") (pintype "passive"))
    )
    (net (code "43") (name "/P00.9") (class "Default")
      (node (ref "U1") (pin "109") (pinfunction "P00.9_109") (pintype "passive"))
    )
    (net (code "44") (name "/P02.8") (class "Default")
      (node (ref "U1") (pin "101") (pinfunction "P02.8_101") (pintype "passive"))
    )
    (net (code "45") (name "/P10.2") (class "Default")
      (node (ref "U1") (pin "86") (pinfunction "P10.2_86") (pintype "passive"))
    )
    (net (code "46") (name "/P11.2") (class "Default")
      (node (ref "J7") (pin "7") (pinfunction "7_7") (pintype "passive"))
      (node (ref "U1") (pin "79") (pinfunction "P11.2_79") (pintype "passive"))
    )
    (net (code "47") (name "/P11.3") (class "Default")
      (node (ref "J7") (pin "14") (pinfunction "14_14") (pintype "passive"))
      (node (ref "U1") (pin "80") (pinfunction "P11.3_80") (pintype "passive"))
    )
    (net (code "48") (name "/P11.6") (class "Default")
      (node (ref "U1") (pin "82") (pinfunction "P11.6_82") (pintype "passive"))
    )
    (net (code "49") (name "/P11.9") (class "Default")
      (node (ref "U1") (pin "81") (pinfunction "P11.9_81") (pintype "passive"))
    )
    (net (code "50") (name "/P11.10") (class "Default")
      (node (ref "U1") (pin "84") (pinfunction "P11.10_84") (pintype "passive"))
    )
    (net (code "51") (name "/P11.11") (class "Default")
      (node (ref "U1") (pin "85") (pinfunction "P11.11_85") (pintype "passive"))
    )
    (net (code "52") (name "/P11.12") (class "Default")
      (node (ref "U1") (pin "83") (pinfunction "P11.12_83") (pintype "passive"))
    )
    (net (code "53") (name "/PWM_Motor1+") (class "Default")
      (node (ref "J2") (pin "5") (pinfunction "5_5") (pintype "passive"))
      (node (ref "JP1") (pin "4") (pinfunction "4_4") (pintype "passive"))
      (node (ref "U1") (pin "24") (pinfunction "P32.4_24") (pintype "passive"))
    )
    (net (code "54") (name "/PWM_Motor1-") (class "Default")
      (node (ref "J2") (pin "4") (pinfunction "4_4") (pintype "passive"))
      (node (ref "JP1") (pin "5") (pinfunction "5_5") (pintype "passive"))
      (node (ref "U1") (pin "29") (pinfunction "P23.1_29") (pintype "passive"))
    )
    (net (code "55") (name "/PWM_Motor2+") (class "Default")
      (node (ref "J2") (pin "3") (pinfunction "3_3") (pintype "passive"))
      (node (ref "JP1") (pin "6") (pinfunction "6_6") (pintype "passive"))
      (node (ref "U1") (pin "32") (pinfunction "P22.3_32") (pintype "passive"))
    )
    (net (code "56") (name "/PWM_Motor2-") (class "Default")
      (node (ref "J2") (pin "2") (pinfunction "2_2") (pintype "passive"))
      (node (ref "JP1") (pin "7") (pinfunction "7_7") (pintype "passive"))
      (node (ref "U1") (pin "35") (pinfunction "P21.2_35") (pintype "passive"))
    )
    (net (code "57") (name "/PWM_ServoMotor") (class "Default")
      (node (ref "D1") (pin "1") (pinfunction "C_1") (pintype "passive"))
      (node (ref "R1") (pin "1") (pinfunction "1_1") (pintype "passive"))
      (node (ref "U1") (pin "54") (pinfunction "P20.8_54") (pintype "passive"))
    )
    (net (code "58") (name "/SW1") (class "Default")
      (node (ref "RN2") (pin "4") (pinfunction "4_4") (pintype "passive"))
      (node (ref "SW2") (pin "1") (pinfunction "1_1") (pintype "passive"))
      (node (ref "U1") (pin "22") (pinfunction "P33.11_22") (pintype "passive"))
    )
    (net (code "59") (name "/SW2") (class "Default")
      (node (ref "RN2") (pin "3") (pinfunction "3_3") (pintype "passive"))
      (node (ref "SW2") (pin "2") (pinfunction "2_2") (pintype "passive"))
      (node (ref "U1") (pin "19") (pinfunction "P33.7_19") (pintype "passive"))
    )
    (net (code "60") (name "/SW3") (class "Default")
      (node (ref "RN2") (pin "2") (pinfunction "2_2") (pintype "passive"))
      (node (ref "SW2") (pin "3") (pinfunction "3_3") (pintype "passive"))
      (node (ref "U1") (pin "20") (pinfunction "P33.9_20") (pintype "passive"))
    )
    (net (code "61") (name "/SW4") (class "Default")
      (node (ref "RN2") (pin "1") (pinfunction "1_1") (pintype "passive"))
      (node (ref "SW2") (pin "4") (pinfunction "4_4") (pintype "passive"))
      (node (ref "U1") (pin "17") (pinfunction "P33.6_17") (pintype "passive"))
    )
    (net (code "62") (name "/TFT_CS") (class "Default")
      (node (ref "LCD1") (pin "3") (pinfunction "CS_3") (pintype "passive"))
      (node (ref "U1") (pin "60") (pinfunction "P20.14_60") (pintype "passive"))
    )
    (net (code "63") (name "/TFT_D{slash}C") (class "Default")
      (node (ref "LCD1") (pin "6") (pinfunction "D/C_6") (pintype "passive"))
      (node (ref "U1") (pin "58") (pinfunction "P20.12_58") (pintype "passive"))
    )
    (net (code "64") (name "/TFT_RST") (class "Default")
      (node (ref "LCD1") (pin "7") (pinfunction "RST_7") (pintype "passive"))
      (node (ref "U1") (pin "59") (pinfunction "P20.13_59") (pintype "passive"))
    )
    (net (code "65") (name "/TFT_SCK") (class "Default")
      (node (ref "LCD1") (pin "4") (pinfunction "SCK_4") (pintype "passive"))
      (node (ref "U1") (pin "57") (pinfunction "P20.11_57") (pintype "passive"))
    )
    (net (code "66") (name "/TFT_SDI") (class "Default")
      (node (ref "LCD1") (pin "5") (pinfunction "SDI_5") (pintype "passive"))
      (node (ref "U1") (pin "56") (pinfunction "P20.10_56") (pintype "passive"))
    )
    (net (code "67") (name "/TOF_RXD") (class "Default")
      (node (ref "J3") (pin "5") (pinfunction "5_5") (pintype "passive"))
      (node (ref "U1") (pin "100") (pinfunction "P00.0_100") (pintype "passive"))
    )
    (net (code "68") (name "/TOF_TXD") (class "Default")
      (node (ref "J3") (pin "6") (pinfunction "6_6") (pintype "passive"))
      (node (ref "U1") (pin "99") (pinfunction "P00.1_99") (pintype "passive"))
    )
    (net (code "69") (name "/VCC_ServoMotor") (class "Default")
      (node (ref "C1") (pin "1") (pinfunction "1_1") (pintype "passive"))
      (node (ref "J1") (pin "2") (pinfunction "2_2") (pintype "passive"))
      (node (ref "L1") (pin "2") (pinfunction "2_2") (pintype "passive"))
      (node (ref "R9") (pin "1") (pinfunction "1_1") (pintype "passive"))
    )
    (net (code "70") (name "7.2V") (class "Default")
      (node (ref "C2") (pin "1") (pinfunction "1_1") (pintype "passive"))
      (node (ref "C3") (pin "1") (pinfunction "1_1") (pintype "passive"))
      (node (ref "C6") (pin "1") (pinfunction "1_1") (pintype "passive"))
      (node (ref "C7") (pin "1") (pinfunction "1_1") (pintype "passive"))
      (node (ref "F1") (pin "2") (pinfunction "2_2") (pintype "passive"))
      (node (ref "R10") (pin "1") (pinfunction "1_1") (pintype "passive"))
      (node (ref "R11") (pin "1") (pinfunction "1_1") (pintype "passive"))
      (node (ref "R12") (pin "1") (pinfunction "1_1") (pintype "passive"))
      (node (ref "R8") (pin "2") (pinfunction "2_2") (pintype "passive"))
      (node (ref "U2") (pin "4") (pinfunction "IN_4") (pintype "passive"))
      (node (ref "U4") (pin "1") (pinfunction "VIN_1") (pintype "passive"))
    )
    (net (code "71") (name "GND") (class "Default")
      (node (ref "C1") (pin "2") (pinfunction "2_2") (pintype "passive"))
      (node (ref "C10") (pin "2") (pinfunction "2_2") (pintype "passive"))
      (node (ref "C2") (pin "2") (pinfunction "2_2") (pintype "passive"))
      (node (ref "C3") (pin "2") (pinfunction "2_2") (pintype "passive"))
      (node (ref "C4") (pin "2") (pinfunction "2_2") (pintype "passive"))
      (node (ref "C5") (pin "2") (pinfunction "2_2") (pintype "passive"))
      (node (ref "C6") (pin "2") (pinfunction "2_2") (pintype "passive"))
      (node (ref "C7") (pin "2") (pinfunction "2_2") (pintype "passive"))
      (node (ref "C8") (pin "2") (pinfunction "2_2") (pintype "passive"))
      (node (ref "C9") (pin "1") (pinfunction "1_1") (pintype "passive"))
      (node (ref "D1") (pin "2") (pinfunction "A_2") (pintype "passive"))
      (node (ref "D10") (pin "1") (pinfunction "A_1") (pintype "passive"))
      (node (ref "D12") (pin "1") (pinfunction "A_1") (pintype "passive"))
      (node (ref "D2") (pin "2") (pinfunction "A_2") (pintype "passive"))
      (node (ref "D3") (pin "2") (pinfunction "A_2") (pintype "passive"))
      (node (ref "D4") (pin "2") (pinfunction "A_2") (pintype "passive"))
      (node (ref "D5") (pin "2") (pinfunction "A_2") (pintype "passive"))
      (node (ref "D6") (pin "2") (pinfunction "A_2") (pintype "passive"))
      (node (ref "D7") (pin "2") (pinfunction "A_2") (pintype "passive"))
      (node (ref "D9") (pin "C") (pinfunction "C_C") (pintype "passive"))
      (node (ref "FM1") (pin "2") (pinfunction "－_2") (pintype "passive"))
      (node (ref "J1") (pin "1") (pinfunction "1_1") (pintype "passive"))
      (node (ref "J11") (pin "2") (pinfunction "2_2") (pintype "passive"))
      (node (ref "J2") (pin "1") (pinfunction "1_1") (pintype "passive"))
      (node (ref "J3") (pin "2") (pinfunction "2_2") (pintype "passive"))
      (node (ref "J4") (pin "1") (pinfunction "1_1") (pintype "passive"))
      (node (ref "J5") (pin "2") (pinfunction "2_2") (pintype "passive"))
      (node (ref "J6") (pin "1") (pinfunction "1_1") (pintype "passive"))
      (node (ref "J7") (pin "10") (pinfunction "10_10") (pintype "passive"))
      (node (ref "J7") (pin "12") (pinfunction "12_12") (pintype "passive"))
      (node (ref "J8") (pin "1") (pinfunction "1_1") (pintype "passive"))
      (node (ref "JP1") (pin "8") (pinfunction "8_8") (pintype "passive"))
      (node (ref "K1") (pin "A") (pinfunction "A_A") (pintype "passive"))
      (node (ref "K2") (pin "A") (pinfunction "A_A") (pintype "passive"))
      (node (ref "K3") (pin "A") (pinfunction "A_A") (pintype "passive"))
      (node (ref "K4") (pin "A") (pinfunction "A_A") (pintype "passive"))
      (node (ref "K5") (pin "A") (pinfunction "A_A") (pintype "passive"))
      (node (ref "LCD1") (pin "1") (pinfunction "GND_1") (pintype "passive"))
      (node (ref "P1") (pin "1") (pinfunction "1_1") (pintype "passive"))
      (node (ref "R14") (pin "2") (pinfunction "2_2") (pintype "passive"))
      (node (ref "R24") (pin "1") (pinfunction "1_1") (pintype "passive"))
      (node (ref "R7") (pin "1") (pinfunction "1_1") (pintype "passive"))
      (node (ref "SW2") (pin "5") (pinfunction "5_5") (pintype "passive"))
      (node (ref "SW2") (pin "6") (pinfunction "6_6") (pintype "passive"))
      (node (ref "SW2") (pin "7") (pinfunction "7_7") (pintype "passive"))
      (node (ref "SW2") (pin "8") (pinfunction "8_8") (pintype "passive"))
      (node (ref "U1") (pin "40") (pinfunction "GND_40") (pintype "passive"))
      (node (ref "U1") (pin "43") (pinfunction "GND_43") (pintype "passive"))
      (node (ref "U2") (pin "7") (pinfunction "GND_7") (pintype "passive"))
      (node (ref "U2") (pin "8") (pinfunction "GND_8") (pintype "passive"))
      (node (ref "U3") (pin "1") (pinfunction "GND_1") (pintype "passive"))
      (node (ref "U4") (pin "3") (pinfunction "GND_3") (pintype "passive"))
      (node (ref "U4") (pin "5") (pinfunction "ON#/OFF_5") (pintype "passive"))
      (node (ref "U4") (pin "6") (pinfunction "GND_6") (pintype "passive"))
      (node (ref "U5") (pin "1") (pinfunction "GND_1") (pintype "passive"))
      (node (ref "U5") (pin "2") (pinfunction "EN_2") (pintype "passive"))
    )
    (net (code "72") (name "Net-(C11-Pad2)") (class "Default")
      (node (ref "C11") (pin "2") (pinfunction "2_2") (pintype "passive"))
      (node (ref "R24") (pin "2") (pinfunction "2_2") (pintype "passive"))
    )
    (net (code "73") (name "Net-(D8-A)") (class "Default")
      (node (ref "D8") (pin "1") (pinfunction "A_1") (pintype "passive"))
      (node (ref "SW1") (pin "2") (pinfunction "C_2") (pintype "passive"))
    )
    (net (code "74") (name "Net-(D8-C)") (class "Default")
      (node (ref "D8") (pin "2") (pinfunction "C_2") (pintype "passive"))
      (node (ref "F1") (pin "1") (pinfunction "1_1") (pintype "passive"))
    )
    (net (code "75") (name "Net-(D9-PadA)") (class "Default")
      (node (ref "D9") (pin "A") (pinfunction "A_A") (pintype "passive"))
      (node (ref "R8") (pin "1") (pinfunction "1_1") (pintype "passive"))
    )
    (net (code "76") (name "Net-(D10-C)") (class "Default")
      (node (ref "D10") (pin "2") (pinfunction "C_2") (pintype "passive"))
      (node (ref "L1") (pin "1") (pinfunction "1_1") (pintype "passive"))
      (node (ref "U2") (pin "5") (pinfunction "SW_5") (pintype "passive"))
      (node (ref "U2") (pin "6") (pinfunction "SW_6") (pintype "passive"))
    )
    (net (code "77") (name "Net-(D11-A)") (class "Default")
      (node (ref "D11") (pin "1") (pinfunction "A_1") (pintype "passive"))
      (node (ref "F3") (pin "2") (pinfunction "2_2") (pintype "passive"))
    )
    (net (code "78") (name "Net-(D12-C)") (class "Default")
      (node (ref "D12") (pin "2") (pinfunction "C_2") (pintype "passive"))
      (node (ref "L2") (pin "2") (pinfunction "2_2") (pintype "passive"))
      (node (ref "U4") (pin "2") (pinfunction "OUTPUT_2") (pintype "passive"))
    )
    (net (code "79") (name "Net-(FM1-+)") (class "Default")
      (node (ref "FM1") (pin "1") (pinfunction "+_1") (pintype "passive"))
      (node (ref "Q1") (pin "3") (pinfunction "C_3") (pintype "passive"))
    )
    (net (code "80") (name "Net-(J1-Pad3)") (class "Default")
      (node (ref "J1") (pin "3") (pinfunction "3_3") (pintype "passive"))
      (node (ref "R1") (pin "2") (pinfunction "2_2") (pintype "passive"))
    )
    (net (code "81") (name "Net-(J4-Pad3)") (class "Default")
      (node (ref "J4") (pin "3") (pinfunction "3_3") (pintype "passive"))
      (node (ref "RN1") (pin "4") (pinfunction "4_4") (pintype "passive"))
    )
    (net (code "82") (name "Net-(J4-Pad4)") (class "Default")
      (node (ref "J4") (pin "4") (pinfunction "4_4") (pintype "passive"))
      (node (ref "RN1") (pin "3") (pinfunction "3_3") (pintype "passive"))
    )
    (net (code "83") (name "Net-(J4-Pad5)") (class "Default")
      (node (ref "J4") (pin "5") (pinfunction "5_5") (pintype "passive"))
      (node (ref "RN1") (pin "2") (pinfunction "2_2") (pintype "passive"))
    )
    (net (code "84") (name "Net-(J4-Pad6)") (class "Default")
      (node (ref "J4") (pin "6") (pinfunction "6_6") (pintype "passive"))
      (node (ref "RN1") (pin "1") (pinfunction "1_1") (pintype "passive"))
    )
    (net (code "85") (name "Net-(J4-Pad7)") (class "Default")
      (node (ref "J4") (pin "7") (pinfunction "7_7") (pintype "passive"))
      (node (ref "R4") (pin "2") (pinfunction "2_2") (pintype "passive"))
    )
    (net (code "86") (name "Net-(J4-Pad8)") (class "Default")
      (node (ref "J4") (pin "8") (pinfunction "8_8") (pintype "passive"))
      (node (ref "R3") (pin "2") (pinfunction "2_2") (pintype "passive"))
    )
    (net (code "87") (name "Net-(J11-Pad3)") (class "Default")
      (node (ref "J11") (pin "3") (pinfunction "3_3") (pintype "passive"))
      (node (ref "R6") (pin "2") (pinfunction "2_2") (pintype "passive"))
    )
    (net (code "88") (name "Net-(J11-Pad4)") (class "Default")
      (node (ref "J11") (pin "4") (pinfunction "4_4") (pintype "passive"))
      (node (ref "R5") (pin "2") (pinfunction "2_2") (pintype "passive"))
    )
    (net (code "89") (name "Net-(LCD1-3.3V)") (class "Default")
      (node (ref "LCD1") (pin "2") (pinfunction "3.3V_2") (pintype "passive"))
      (node (ref "R2") (pin "2") (pinfunction "2_2") (pintype "passive"))
    )
    (net (code "90") (name "Net-(Q1-B)") (class "Default")
      (node (ref "Q1") (pin "2") (pinfunction "B_2") (pintype "passive"))
      (node (ref "R15") (pin "2") (pinfunction "2_2") (pintype "passive"))
      (node (ref "R16") (pin "2") (pinfunction "2_2") (pintype "passive"))
    )
    (net (code "91") (name "Net-(R12-Pad2)") (class "Default")
      (node (ref "R12") (pin "2") (pinfunction "2_2") (pintype "passive"))
      (node (ref "R13") (pin "1") (pinfunction "1_1") (pintype "passive"))
      (node (ref "R14") (pin "1") (pinfunction "1_1") (pintype "passive"))
    )
    (net (code "92") (name "Net-(U2-EN)") (class "Default")
      (node (ref "R10") (pin "2") (pinfunction "2_2") (pintype "passive"))
      (node (ref "U2") (pin "2") (pinfunction "EN_2") (pintype "passive"))
    )
    (net (code "93") (name "Net-(U2-FB)") (class "Default")
      (node (ref "R7") (pin "2") (pinfunction "2_2") (pintype "passive"))
      (node (ref "R9") (pin "2") (pinfunction "2_2") (pintype "passive"))
      (node (ref "U2") (pin "1") (pinfunction "FB_1") (pintype "passive"))
    )
    (net (code "94") (name "Net-(U2-OCSET)") (class "Default")
      (node (ref "R11") (pin "2") (pinfunction "2_2") (pintype "passive"))
      (node (ref "U2") (pin "3") (pinfunction "OCSET_3") (pintype "passive"))
    )
    (net (code "95") (name "Net-(U4-FB)") (class "Default")
      (node (ref "C8") (pin "1") (pinfunction "1_1") (pintype "passive"))
      (node (ref "F2") (pin "1") (pinfunction "1_1") (pintype "passive"))
      (node (ref "L2") (pin "1") (pinfunction "1_1") (pintype "passive"))
      (node (ref "U4") (pin "4") (pinfunction "FB_4") (pintype "passive"))
    )
    (net (code "96") (name "Net-(U5-IN)") (class "Default")
      (node (ref "C9") (pin "2") (pinfunction "2_2") (pintype "passive"))
      (node (ref "F3") (pin "1") (pinfunction "1_1") (pintype "passive"))
      (node (ref "U5") (pin "3") (pinfunction "IN/2_3") (pintype "passive"))
      (node (ref "U5") (pin "4") (pinfunction "IN_4") (pintype "passive"))
    )
    (net (code "97") (name "Net-(U5-OUT)") (class "Default")
      (node (ref "C10") (pin "1") (pinfunction "1_1") (pintype "passive"))
      (node (ref "C11") (pin "1") (pinfunction "1_1") (pintype "passive"))
      (node (ref "R22") (pin "1") (pinfunction "1_1") (pintype "passive"))
      (node (ref "R23") (pin "2") (pinfunction "2_2") (pintype "passive"))
      (node (ref "U5") (pin "5") (pinfunction "OUT/2_5") (pintype "passive"))
      (node (ref "U5") (pin "6") (pinfunction "OUT_6") (pintype "passive"))
      (node (ref "U5") (pin "7") (pinfunction "SENSEFB_7") (pintype "passive"))
    )
    (net (code "98") (name "Net-(U5-RESET)") (class "Default")
      (node (ref "R23") (pin "1") (pinfunction "1_1") (pintype "passive"))
      (node (ref "U5") (pin "8") (pinfunction "RESET_8") (pintype "passive"))
    )
    (net (code "99") (name "VCC3.3_MCU") (class "Default")
      (node (ref "R22") (pin "2") (pinfunction "2_2") (pintype "passive"))
      (node (ref "U1") (pin "46") (pinfunction "3V3_46") (pintype "passive"))
      (node (ref "U1") (pin "6") (pinfunction "VREF+_6") (pintype "passive"))
    )
    (net (code "100") (name "VCC_3.3V") (class "Default")
      (node (ref "C5") (pin "1") (pinfunction "1_1") (pintype "passive"))
      (node (ref "J3") (pin "1") (pinfunction "1_1") (pintype "passive"))
      (node (ref "J5") (pin "1") (pinfunction "1_1") (pintype "passive"))
      (node (ref "J7") (pin "11") (pinfunction "11_11") (pintype "passive"))
      (node (ref "Q1") (pin "1") (pinfunction "E_1") (pintype "passive"))
      (node (ref "R15") (pin "1") (pinfunction "1_1") (pintype "passive"))
      (node (ref "R17") (pin "2") (pinfunction "2_2") (pintype "passive"))
      (node (ref "R18") (pin "2") (pinfunction "2_2") (pintype "passive"))
      (node (ref "R19") (pin "2") (pinfunction "2_2") (pintype "passive"))
      (node (ref "R2") (pin "1") (pinfunction "1_1") (pintype "passive"))
      (node (ref "R20") (pin "2") (pinfunction "2_2") (pintype "passive"))
      (node (ref "R21") (pin "2") (pinfunction "2_2") (pintype "passive"))
      (node (ref "RN2") (pin "5") (pinfunction "5_5") (pintype "passive"))
      (node (ref "RN2") (pin "6") (pinfunction "6_6") (pintype "passive"))
      (node (ref "RN2") (pin "7") (pinfunction "7_7") (pintype "passive"))
      (node (ref "RN2") (pin "8") (pinfunction "8_8") (pintype "passive"))
      (node (ref "U3") (pin "2") (pinfunction "Out_2") (pintype "passive"))
      (node (ref "U3") (pin "4") (pinfunction "TAB_4") (pintype "passive"))
    )
    (net (code "101") (name "VCC_5V") (class "Default")
      (node (ref "C4") (pin "1") (pinfunction "1_1") (pintype "passive"))
      (node (ref "D11") (pin "2") (pinfunction "C_2") (pintype "passive"))
      (node (ref "F2") (pin "2") (pinfunction "2_2") (pintype "passive"))
      (node (ref "J11") (pin "1") (pinfunction "1_1") (pintype "passive"))
      (node (ref "J4") (pin "2") (pinfunction "2_2") (pintype "passive"))
      (node (ref "J6") (pin "6") (pinfunction "6_6") (pintype "passive"))
      (node (ref "J8") (pin "6") (pinfunction "6_6") (pintype "passive"))
      (node (ref "U3") (pin "3") (pinfunction "In_3") (pintype "passive"))
    )
    (net (code "102") (name "unconnected-(J2-Pad6)") (class "Default")
      (node (ref "J2") (pin "6") (pinfunction "6_6") (pintype "passive"))
    )
    (net (code "103") (name "unconnected-(J2-Pad7)") (class "Default")
      (node (ref "J2") (pin "7") (pinfunction "7_7") (pintype "passive"))
    )
    (net (code "104") (name "unconnected-(J2-Pad8)") (class "Default")
      (node (ref "J2") (pin "8") (pinfunction "8_8") (pintype "passive"))
    )
    (net (code "105") (name "unconnected-(J6-Pad3)") (class "Default")
      (node (ref "J6") (pin "3") (pinfunction "3_3") (pintype "passive"))
    )
    (net (code "106") (name "unconnected-(J6-Pad4)") (class "Default")
      (node (ref "J6") (pin "4") (pinfunction "4_4") (pintype "passive"))
    )
    (net (code "107") (name "unconnected-(J7-Pad1)") (class "Default")
      (node (ref "J7") (pin "1") (pinfunction "1_1") (pintype "passive"))
    )
    (net (code "108") (name "unconnected-(J7-Pad2)") (class "Default")
      (node (ref "J7") (pin "2") (pinfunction "2_2") (pintype "passive"))
    )
    (net (code "109") (name "unconnected-(J7-Pad19)") (class "Default")
      (node (ref "J7") (pin "19") (pinfunction "19_19") (pintype "passive"))
    )
    (net (code "110") (name "unconnected-(J7-Pad20)") (class "Default")
      (node (ref "J7") (pin "20") (pinfunction "20_20") (pintype "passive"))
    )
    (net (code "111") (name "unconnected-(J8-Pad3)") (class "Default")
      (node (ref "J8") (pin "3") (pinfunction "3_3") (pintype "passive"))
    )
    (net (code "112") (name "unconnected-(J8-Pad4)") (class "Default")
      (node (ref "J8") (pin "4") (pinfunction "4_4") (pintype "passive"))
    )
    (net (code "113") (name "unconnected-(JP1-Pad1)") (class "Default")
      (node (ref "JP1") (pin "1") (pinfunction "1_1") (pintype "passive"))
    )
    (net (code "114") (name "unconnected-(JP1-Pad2)") (class "Default")
      (node (ref "JP1") (pin "2") (pinfunction "2_2") (pintype "passive"))
    )
    (net (code "115") (name "unconnected-(JP1-Pad3)") (class "Default")
      (node (ref "JP1") (pin "3") (pinfunction "3_3") (pintype "passive"))
    )
    (net (code "116") (name "unconnected-(R7-Pad3)") (class "Default")
      (node (ref "R7") (pin "3") (pinfunction "3_3") (pintype "passive"))
    )
    (net (code "117") (name "unconnected-(SW1-ON-Pad1)") (class "Default")
      (node (ref "SW1") (pin "1") (pinfunction "ON_1") (pintype "passive"))
    )
    (net (code "118") (name "unconnected-(U1A-AN24-Pad125)") (class "Default")
      (node (ref "U1") (pin "125") (pinfunction "AN24_125") (pintype "passive"))
    )
    (net (code "119") (name "unconnected-(U1A-AN36-Pad122)") (class "Default")
      (node (ref "U1") (pin "122") (pinfunction "AN36_122") (pintype "passive"))
    )
    (net (code "120") (name "unconnected-(U1A-AN39-Pad119)") (class "Default")
      (node (ref "U1") (pin "119") (pinfunction "AN39_119") (pintype "passive"))
    )
    (net (code "121") (name "unconnected-(U1A-AN46-Pad116)") (class "Default")
      (node (ref "U1") (pin "116") (pinfunction "AN46_116") (pintype "passive"))
    )
    (net (code "122") (name "unconnected-(U1A-AN49-Pad113)") (class "Default")
      (node (ref "U1") (pin "113") (pinfunction "AN49_113") (pintype "passive"))
    )
    (net (code "123") (name "unconnected-(U1B-AN13-Pad126)") (class "Default")
      (node (ref "U1") (pin "126") (pinfunction "AN13_126") (pintype "passive"))
    )
    (net (code "124") (name "unconnected-(U1B-AN16-Pad124)") (class "Default")
      (node (ref "U1") (pin "124") (pinfunction "AN16_124") (pintype "passive"))
    )
    (net (code "125") (name "unconnected-(U1B-AN17-Pad123)") (class "Default")
      (node (ref "U1") (pin "123") (pinfunction "AN17_123") (pintype "passive"))
    )
    (net (code "126") (name "unconnected-(U1B-AN20-Pad127)") (class "Default")
      (node (ref "U1") (pin "127") (pinfunction "AN20_127") (pintype "passive"))
    )
    (net (code "127") (name "unconnected-(U1B-AN25-Pad120)") (class "Default")
      (node (ref "U1") (pin "120") (pinfunction "AN25_120") (pintype "passive"))
    )
    (net (code "128") (name "unconnected-(U1B-AN35-Pad121)") (class "Default")
      (node (ref "U1") (pin "121") (pinfunction "AN35_121") (pintype "passive"))
    )
    (net (code "129") (name "unconnected-(U1B-AN37-Pad117)") (class "Default")
      (node (ref "U1") (pin "117") (pinfunction "AN37_117") (pintype "passive"))
    )
    (net (code "130") (name "unconnected-(U1B-AN38-Pad118)") (class "Default")
      (node (ref "U1") (pin "118") (pinfunction "AN38_118") (pintype "passive"))
    )
    (net (code "131") (name "unconnected-(U1B-AN44-Pad114)") (class "Default")
      (node (ref "U1") (pin "114") (pinfunction "AN44_114") (pintype "passive"))
    )
    (net (code "132") (name "unconnected-(U1B-AN45-Pad115)") (class "Default")
      (node (ref "U1") (pin "115") (pinfunction "AN45_115") (pintype "passive"))
    )
    (net (code "133") (name "unconnected-(U1B-AN47-Pad111)") (class "Default")
      (node (ref "U1") (pin "111") (pinfunction "AN47_111") (pintype "passive"))
    )
    (net (code "134") (name "unconnected-(U1B-AN48-Pad112)") (class "Default")
      (node (ref "U1") (pin "112") (pinfunction "AN48_112") (pintype "passive"))
    )
    (net (code "135") (name "unconnected-(U1B-P00.12-Pad108)") (class "Default")
      (node (ref "U1") (pin "108") (pinfunction "P00.12_108") (pintype "passive"))
    )
    (net (code "136") (name "unconnected-(U1B-P10.6{slash}#5-Pad90)") (class "Default")
      (node (ref "U1") (pin "90") (pinfunction "P10.6/#5_90") (pintype "passive"))
    )
    (net (code "137") (name "unconnected-(U1C-P10.5{slash}#4-Pad87)") (class "Default")
      (node (ref "U1") (pin "87") (pinfunction "P10.5/#4_87") (pintype "passive"))
    )
    (net (code "138") (name "unconnected-(U1C-P13.0-Pad74)") (class "Default")
      (node (ref "U1") (pin "74") (pinfunction "P13.0_74") (pintype "passive"))
    )
    (net (code "139") (name "unconnected-(U1C-P13.3-Pad78)") (class "Default")
      (node (ref "U1") (pin "78") (pinfunction "P13.3_78") (pintype "passive"))
    )
    (net (code "140") (name "unconnected-(U1C-P14.2{slash}#2-Pad71)") (class "Default")
      (node (ref "U1") (pin "71") (pinfunction "P14.2/#2_71") (pintype "passive"))
    )
    (net (code "141") (name "unconnected-(U1C-P14.3{slash}#3-Pad73)") (class "Default")
      (node (ref "U1") (pin "73") (pinfunction "P14.3/#3_73") (pintype "passive"))
    )
    (net (code "142") (name "unconnected-(U1C-P14.4{slash}#6-Pad70)") (class "Default")
      (node (ref "U1") (pin "70") (pinfunction "P14.4/#6_70") (pintype "passive"))
    )
    (net (code "143") (name "unconnected-(U1C-P14.5{slash}#1-Pad72)") (class "Default")
      (node (ref "U1") (pin "72") (pinfunction "P14.5/#1_72") (pintype "passive"))
    )
    (net (code "144") (name "unconnected-(U1C-P14.6{slash}#0-Pad75)") (class "Default")
      (node (ref "U1") (pin "75") (pinfunction "P14.6/#0_75") (pintype "passive"))
    )
    (net (code "145") (name "unconnected-(U1C-P15.0-Pad65)") (class "Default")
      (node (ref "U1") (pin "65") (pinfunction "P15.0_65") (pintype "passive"))
    )
    (net (code "146") (name "unconnected-(U1C-P15.2-Pad67)") (class "Default")
      (node (ref "U1") (pin "67") (pinfunction "P15.2_67") (pintype "passive"))
    )
    (net (code "147") (name "unconnected-(U1C-P15.3-Pad66)") (class "Default")
      (node (ref "U1") (pin "66") (pinfunction "P15.3_66") (pintype "passive"))
    )
    (net (code "148") (name "unconnected-(U1C-P15.7-Pad69)") (class "Default")
      (node (ref "U1") (pin "69") (pinfunction "P15.7_69") (pintype "passive"))
    )
    (net (code "149") (name "unconnected-(U1C-P15.8-Pad68)") (class "Default")
      (node (ref "U1") (pin "68") (pinfunction "P15.8_68") (pintype "passive"))
    )
    (net (code "150") (name "unconnected-(U1D-AN2-Pad11)") (class "Default")
      (node (ref "U1") (pin "11") (pinfunction "AN2_11") (pintype "passive"))
    )
    (net (code "151") (name "unconnected-(U1D-AN8-Pad8)") (class "Default")
      (node (ref "U1") (pin "8") (pinfunction "AN8_8") (pintype "passive"))
    )
    (net (code "152") (name "unconnected-(U1D-AN10-Pad3)") (class "Default")
      (node (ref "U1") (pin "3") (pinfunction "AN10_3") (pintype "passive"))
    )
    (net (code "153") (name "unconnected-(U1D-AN11-Pad4)") (class "Default")
      (node (ref "U1") (pin "4") (pinfunction "AN11_4") (pintype "passive"))
    )
    (net (code "154") (name "unconnected-(U1D-AN12-Pad1)") (class "Default")
      (node (ref "U1") (pin "1") (pinfunction "AN12_1") (pintype "passive"))
    )
    (net (code "155") (name "unconnected-(U1D-P33.4-Pad15)") (class "Default")
      (node (ref "U1") (pin "15") (pinfunction "P33.4_15") (pintype "passive"))
    )
    (net (code "156") (name "unconnected-(U1D-P33.5-Pad16)") (class "Default")
      (node (ref "U1") (pin "16") (pinfunction "P33.5_16") (pintype "passive"))
    )
    (net (code "157") (name "unconnected-(U1D-P33.8-Pad18)") (class "Default")
      (node (ref "U1") (pin "18") (pinfunction "P33.8_18") (pintype "passive"))
    )
    (net (code "158") (name "unconnected-(U1D-P33.10-Pad21)") (class "Default")
      (node (ref "U1") (pin "21") (pinfunction "P33.10_21") (pintype "passive"))
    )
    (net (code "159") (name "unconnected-(U1E-ESR0-Pad51)") (class "Default")
      (node (ref "U1") (pin "51") (pinfunction "ESR0_51") (pintype "passive"))
    )
    (net (code "160") (name "unconnected-(U1E-P14.0{slash}TX-Pad37)") (class "Default")
      (node (ref "U1") (pin "37") (pinfunction "P14.0/TX_37") (pintype "passive"))
    )
    (net (code "161") (name "unconnected-(U1E-P14.1{slash}RX-Pad34)") (class "Default")
      (node (ref "U1") (pin "34") (pinfunction "P14.1/RX_34") (pintype "passive"))
    )
    (net (code "162") (name "unconnected-(U1E-P20.6-Pad52)") (class "Default")
      (node (ref "U1") (pin "52") (pinfunction "P20.6_52") (pintype "passive"))
    )
    (net (code "163") (name "unconnected-(U1E-P20.9-Pad55)") (class "Default")
      (node (ref "U1") (pin "55") (pinfunction "P20.9_55") (pintype "passive"))
    )
    (net (code "164") (name "unconnected-(U1E-P32.0{slash}VG1N-Pad26)") (class "Default")
      (node (ref "U1") (pin "26") (pinfunction "P32.0/VG1N_26") (pintype "passive"))
    )
    (net (code "165") (name "unconnected-(U1E-PORST-Pad33)") (class "Default")
      (node (ref "U1") (pin "33") (pinfunction "PORST_33") (pintype "passive"))
    )
    (net (code "166") (name "unconnected-(U1E-TCK-Pad42)") (class "Default")
      (node (ref "U1") (pin "42") (pinfunction "TCK_42") (pintype "passive"))
    )
    (net (code "167") (name "unconnected-(U1E-TDO{slash}P21.7-Pad39)") (class "Default")
      (node (ref "U1") (pin "39") (pinfunction "TDO/P21.7_39") (pintype "passive"))
    )
    (net (code "168") (name "unconnected-(U1E-TMS-Pad45)") (class "Default")
      (node (ref "U1") (pin "45") (pinfunction "TMS_45") (pintype "passive"))
    )
    (net (code "169") (name "unconnected-(U1E-TRST-Pad36)") (class "Default")
      (node (ref "U1") (pin "36") (pinfunction "TRST_36") (pintype "passive"))
    )
    (net (code "170") (name "unconnected-(U1E-VGATE1P-Pad25)") (class "Default")
      (node (ref "U1") (pin "25") (pinfunction "VGATE1P_25") (pintype "passive"))
    )
    (net (code "171") (name "unconnected-(U1F-ESR1-Pad50)") (class "Default")
      (node (ref "U1") (pin "50") (pinfunction "ESR1_50") (pintype "passive"))
    )
    (net (code "172") (name "unconnected-(U1F-P20.7-Pad53)") (class "Default")
      (node (ref "U1") (pin "53") (pinfunction "P20.7_53") (pintype "passive"))
    )
    (net (code "173") (name "unconnected-(U1F-P21.3-Pad38)") (class "Default")
      (node (ref "U1") (pin "38") (pinfunction "P21.3_38") (pintype "passive"))
    )
    (net (code "174") (name "unconnected-(U1F-P21.4-Pad41)") (class "Default")
      (node (ref "U1") (pin "41") (pinfunction "P21.4_41") (pintype "passive"))
    )
    (net (code "175") (name "unconnected-(U1F-P21.5-Pad44)") (class "Default")
      (node (ref "U1") (pin "44") (pinfunction "P21.5_44") (pintype "passive"))
    )
    (net (code "176") (name "unconnected-(U1F-P21.~{6}TDI-Pad47)") (class "Default")
      (node (ref "U1") (pin "47") (pinfunction "P21.~{6}TDI_47") (pintype "passive"))
    )
  )
)
